# power_main.net
KiCad netlist of a schematic drawn in Altium Designer
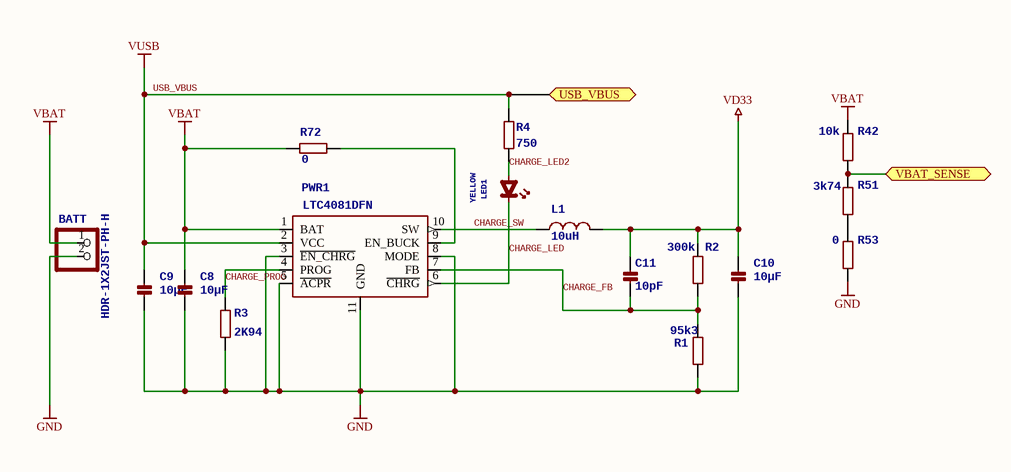
[diagram p0: power_main.SchDoc]

(export (version "E")
  (design (tool "Eeschema 10.0.6"))
  (components
    (comp (ref "BATT")
      (value "HDR-1X2JST-PH-H")
      (footprint "S2B-PH-SM4-TB")
      (description "LI-Poly battery connector")
      (libsource (lib "WunderBar_v101") (part "HEADER-1X2JST-PH-H"))
    )
    (comp (ref "C8")
      (value "10µF")
      (footprint "0603")
      (description "Ceramic Capacitor")
      (libsource (lib "WunderBar_v101") (part "CAP_CERAMIC0603"))
    )
    (comp (ref "C9")
      (value "10µF")
      (footprint "0603")
      (description "Ceramic Capacitor")
      (libsource (lib "WunderBar_v101") (part "CAP_CERAMIC0603"))
    )
    (comp (ref "C10")
      (value "10µF")
      (footprint "0603")
      (description "Ceramic Capacitor")
      (libsource (lib "WunderBar_v101") (part "CAP_CERAMIC0603"))
    )
    (comp (ref "C11")
      (value "10pF")
      (footprint "0402")
      (description "Ceramic Capacitor")
      (libsource (lib "WunderBar_v101") (part "CAP_CERAMIC0402"))
    )
    (comp (ref "L1")
      (value "10uH")
      (footprint "INDUCTOR_40X40")
      (description "Generic inductor")
      (libsource (lib "WunderBar_v101") (part "INDUCTOR40X40MM"))
    )
    (comp (ref "LED1")
      (value "YELLOW")
      (footprint "0402_POLAR")
      (description "LED common")
      (libsource (lib "WunderBar_v101") (part "LED0402"))
    )
    (comp (ref "PWR1")
      (value "LTC4081DFN")
      (footprint "LTC4080_DFN")
      (description "Linear Technology Li-Ion battery charger and buck regulator")
      (libsource (lib "WunderBar_v101") (part "LTC4080DFN"))
    )
    (comp (ref "R1")
      (value "95k3")
      (footprint "0402")
      (description "RESISTOR")
      (libsource (lib "WunderBar_v101") (part "R-EU_0402"))
    )
    (comp (ref "R2")
      (value "300k")
      (footprint "0402")
      (description "RESISTOR")
      (libsource (lib "WunderBar_v101") (part "R-EU_0402"))
    )
    (comp (ref "R3")
      (value "2K94")
      (footprint "0402")
      (description "RESISTOR")
      (libsource (lib "WunderBar_v101") (part "R-EU_0402"))
    )
    (comp (ref "R4")
      (value "750")
      (footprint "0402")
      (description "RESISTOR")
      (libsource (lib "WunderBar_v101") (part "R-EU_0402"))
    )
    (comp (ref "R42")
      (value "10k")
      (footprint "0402")
      (description "RESISTOR")
      (libsource (lib "WunderBar_v101") (part "R-EU_0402"))
    )
    (comp (ref "R51")
      (value "3k74")
      (footprint "0402")
      (description "RESISTOR")
      (libsource (lib "WunderBar_v101") (part "R-EU_0402"))
    )
    (comp (ref "R53")
      (value "0")
      (footprint "0402")
      (description "RESISTOR")
      (libsource (lib "WunderBar_v101") (part "R-EU_0402"))
    )
    (comp (ref "R72")
      (value "0")
      (footprint "0805 v3")
      (description "RESISTOR")
      (libsource (lib "WunderBar_v101") (part "R-EU_0402"))
    )
  )
  (nets
    (net (code "1") (name "/CHARGE_FB") (class "Default")
      (node (ref "C11") (pin "2") (pinfunction "2_2") (pintype "passive"))
      (node (ref "PWR1") (pin "7") (pinfunction "FB_7") (pintype "passive"))
      (node (ref "R1") (pin "2") (pinfunction "2_2") (pintype "passive"))
      (node (ref "R2") (pin "1") (pinfunction "1_1") (pintype "passive"))
    )
    (net (code "2") (name "/CHARGE_LED") (class "Default")
      (node (ref "LED1") (pin "K") (pinfunction "CATHODE_K") (pintype "passive"))
      (node (ref "PWR1") (pin "6") (pinfunction "~{CHRG}_6") (pintype "output"))
    )
    (net (code "3") (name "/CHARGE_LED2") (class "Default")
      (node (ref "LED1") (pin "A") (pinfunction "ANODE_A") (pintype "passive"))
      (node (ref "R4") (pin "1") (pinfunction "1_1") (pintype "passive"))
    )
    (net (code "4") (name "/CHARGE_PROG") (class "Default")
      (node (ref "PWR1") (pin "4") (pinfunction "PROG_4") (pintype "passive"))
      (node (ref "R3") (pin "2") (pinfunction "2_2") (pintype "passive"))
    )
    (net (code "5") (name "/CHARGE_SW") (class "Default")
      (node (ref "L1") (pin "1") (pinfunction "1_1") (pintype "passive"))
      (node (ref "PWR1") (pin "10") (pinfunction "SW_10") (pintype "output"))
    )
    (net (code "6") (name "/VBAT_SENSE") (class "Default")
      (node (ref "R42") (pin "1") (pinfunction "1_1") (pintype "passive"))
      (node (ref "R51") (pin "2") (pinfunction "2_2") (pintype "passive"))
    )
    (net (code "7") (name "GND") (class "Default")
      (node (ref "BATT") (pin "2") (pinfunction "2_2") (pintype "passive"))
      (node (ref "C10") (pin "2") (pinfunction "P2_2") (pintype "passive"))
      (node (ref "C8") (pin "2") (pinfunction "P2_2") (pintype "passive"))
      (node (ref "C9") (pin "2") (pinfunction "P2_2") (pintype "passive"))
      (node (ref "PWR1") (pin "11") (pinfunction "GND_11") (pintype "power_in"))
      (node (ref "PWR1") (pin "3") (pinfunction "~{EN_CHRG}_3") (pintype "passive"))
      (node (ref "PWR1") (pin "5") (pinfunction "~{ACPR}_5") (pintype "passive"))
      (node (ref "PWR1") (pin "8") (pinfunction "MODE_8") (pintype "passive"))
      (node (ref "R1") (pin "1") (pinfunction "1_1") (pintype "passive"))
      (node (ref "R3") (pin "1") (pinfunction "1_1") (pintype "passive"))
      (node (ref "R53") (pin "1") (pinfunction "1_1") (pintype "passive"))
    )
    (net (code "8") (name "Net-(PWR1-EN_BUCK)") (class "Default")
      (node (ref "PWR1") (pin "9") (pinfunction "EN_BUCK_9") (pintype "passive"))
      (node (ref "R72") (pin "1") (pinfunction "1_1") (pintype "passive"))
    )
    (net (code "9") (name "Net-(R51-Pad1)") (class "Default")
      (node (ref "R51") (pin "1") (pinfunction "1_1") (pintype "passive"))
      (node (ref "R53") (pin "2") (pinfunction "2_2") (pintype "passive"))
    )
    (net (code "10") (name "VBAT") (class "Default")
      (node (ref "BATT") (pin "1") (pinfunction "1_1") (pintype "passive"))
      (node (ref "C8") (pin "1") (pinfunction "P1_1") (pintype "passive"))
      (node (ref "PWR1") (pin "1") (pinfunction "BAT_1") (pintype "power_in"))
      (node (ref "R42") (pin "2") (pinfunction "2_2") (pintype "passive"))
      (node (ref "R72") (pin "2") (pinfunction "2_2") (pintype "passive"))
    )
    (net (code "11") (name "VD33") (class "Default")
      (node (ref "C10") (pin "1") (pinfunction "P1_1") (pintype "passive"))
      (node (ref "C11") (pin "1") (pinfunction "1_1") (pintype "passive"))
      (node (ref "L1") (pin "2") (pinfunction "2_2") (pintype "passive"))
      (node (ref "R2") (pin "2") (pinfunction "2_2") (pintype "passive"))
    )
    (net (code "12") (name "VUSB") (class "Default")
      (node (ref "C9") (pin "1") (pinfunction "P1_1") (pintype "passive"))
      (node (ref "PWR1") (pin "2") (pinfunction "VCC_2") (pintype "power_in"))
      (node (ref "R4") (pin "2") (pinfunction "2_2") (pintype "passive"))
    )
  )
)
